# ESP8266_RFID_Schematic.net
KiCad netlist of a schematic drawn in EAGLE
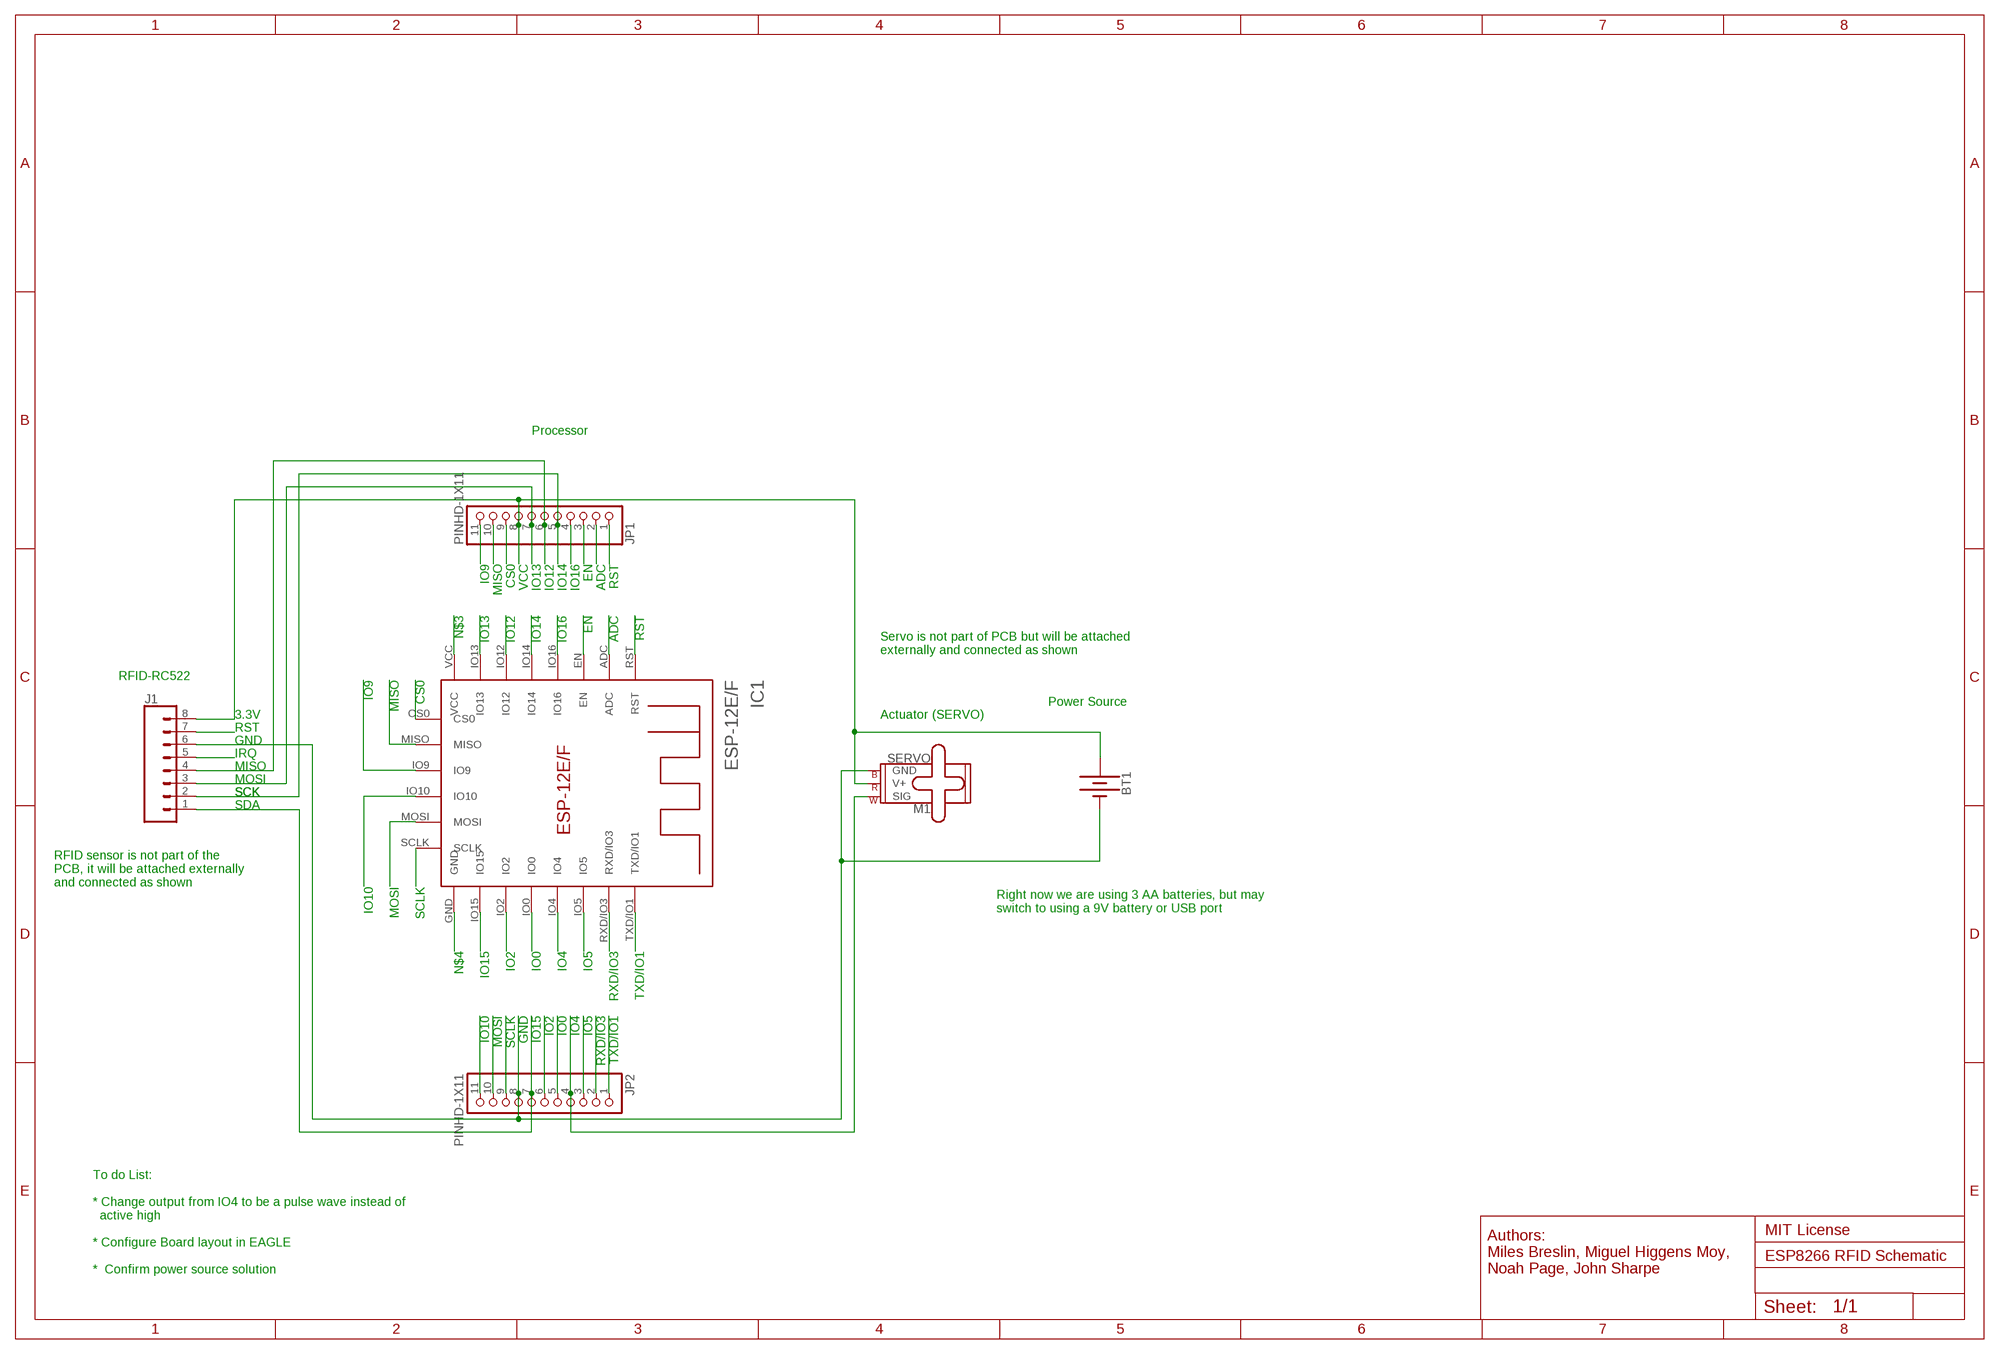
[diagram p0: schematic, sheet 1]

(export (version "E")
  (design (tool "Eeschema 10.0.6"))
  (components
    (comp (ref "BT1")
      (value "BATTERY-AA")
      (footprint "eagle-import:BATTERY-AA")
      (libsource (lib "eagle-import") (part "BATTERY-AA"))
    )
    (comp (ref "IC1")
      (value "ESP-12E/F")
      (footprint "eagle-import:ESP-12E")
      (libsource (lib "eagle-import") (part "ESP-12E/F"))
    )
    (comp (ref "J1")
      (value "CONN_08\"")
      (footprint "eagle-import:1X08")
      (libsource (lib "eagle-import") (part "CONN_08{dblquote}"))
    )
    (comp (ref "JP1")
      (value "PINHD-1X11")
      (footprint "eagle-import:1X11")
      (libsource (lib "eagle-import") (part "PINHD-1X11"))
    )
    (comp (ref "JP2")
      (value "PINHD-1X11")
      (footprint "eagle-import:1X11")
      (libsource (lib "eagle-import") (part "PINHD-1X11"))
    )
    (comp (ref "M1")
      (value "SERVO")
      (footprint "eagle-import:1X03")
      (libsource (lib "eagle-import") (part "SERVO"))
    )
  )
  (nets
    (net (code "1") (name "/ADC") (class "Default")
      (node (ref "IC1") (pin "ADC") (pinfunction "ADC_ADC") (pintype "bidirectional"))
      (node (ref "JP1") (pin "2") (pinfunction "2_2") (pintype "passive"))
    )
    (net (code "2") (name "/CS0") (class "Default")
      (node (ref "IC1") (pin "CS0") (pinfunction "CS0_CS0") (pintype "bidirectional"))
      (node (ref "JP1") (pin "9") (pinfunction "9_9") (pintype "passive"))
    )
    (net (code "3") (name "/EN") (class "Default")
      (node (ref "IC1") (pin "EN") (pinfunction "EN_EN") (pintype "bidirectional"))
      (node (ref "JP1") (pin "3") (pinfunction "3_3") (pintype "passive"))
    )
    (net (code "4") (name "/GND") (class "Default")
      (node (ref "BT1") (pin "GND@1") (pinfunction "-_GND@1") (pintype "power_in"))
      (node (ref "J1") (pin "6") (pinfunction "6_6") (pintype "passive"))
      (node (ref "JP2") (pin "8") (pinfunction "8_8") (pintype "passive"))
      (node (ref "M1") (pin "3") (pinfunction "GND_3") (pintype "bidirectional"))
    )
    (net (code "5") (name "/IO0") (class "Default")
      (node (ref "IC1") (pin "IO0") (pinfunction "IO0_IO0") (pintype "bidirectional"))
      (node (ref "JP2") (pin "5") (pinfunction "5_5") (pintype "passive"))
    )
    (net (code "6") (name "/IO2") (class "Default")
      (node (ref "IC1") (pin "IO2") (pinfunction "IO2_IO2") (pintype "bidirectional"))
      (node (ref "JP2") (pin "6") (pinfunction "6_6") (pintype "passive"))
    )
    (net (code "7") (name "/IO4") (class "Default")
      (node (ref "IC1") (pin "IO4") (pinfunction "IO4_IO4") (pintype "bidirectional"))
      (node (ref "JP2") (pin "4") (pinfunction "4_4") (pintype "passive"))
      (node (ref "M1") (pin "1") (pinfunction "SIG_1") (pintype "bidirectional"))
    )
    (net (code "8") (name "/IO5") (class "Default")
      (node (ref "IC1") (pin "IO5") (pinfunction "IO5_IO5") (pintype "bidirectional"))
      (node (ref "JP2") (pin "3") (pinfunction "3_3") (pintype "passive"))
    )
    (net (code "9") (name "/IO9") (class "Default")
      (node (ref "IC1") (pin "IO9") (pinfunction "IO9_IO9") (pintype "bidirectional"))
      (node (ref "JP1") (pin "11") (pinfunction "11_11") (pintype "passive"))
    )
    (net (code "10") (name "/IO10") (class "Default")
      (node (ref "IC1") (pin "IO10") (pinfunction "IO10_IO10") (pintype "bidirectional"))
      (node (ref "JP2") (pin "11") (pinfunction "11_11") (pintype "passive"))
    )
    (net (code "11") (name "/IO12") (class "Default")
      (node (ref "J1") (pin "4") (pinfunction "4_4") (pintype "passive"))
      (node (ref "JP1") (pin "6") (pinfunction "6_6") (pintype "passive"))
    )
    (net (code "12") (name "/IO13") (class "Default")
      (node (ref "IC1") (pin "IO13") (pinfunction "IO13_IO13") (pintype "bidirectional"))
      (node (ref "J1") (pin "3") (pinfunction "3_3") (pintype "passive"))
      (node (ref "JP1") (pin "7") (pinfunction "7_7") (pintype "passive"))
    )
    (net (code "13") (name "/IO14") (class "Default")
      (node (ref "J1") (pin "2") (pinfunction "2_2") (pintype "passive"))
      (node (ref "JP1") (pin "5") (pinfunction "5_5") (pintype "passive"))
    )
    (net (code "14") (name "/IO15") (class "Default")
      (node (ref "J1") (pin "1") (pinfunction "1_1") (pintype "passive"))
      (node (ref "JP2") (pin "7") (pinfunction "7_7") (pintype "passive"))
    )
    (net (code "15") (name "/IO16") (class "Default")
      (node (ref "IC1") (pin "IO16") (pinfunction "IO16_IO16") (pintype "bidirectional"))
      (node (ref "JP1") (pin "4") (pinfunction "4_4") (pintype "passive"))
    )
    (net (code "16") (name "/MISO") (class "Default")
      (node (ref "IC1") (pin "MISO") (pinfunction "MISO_MISO") (pintype "bidirectional"))
      (node (ref "JP1") (pin "10") (pinfunction "10_10") (pintype "passive"))
    )
    (net (code "17") (name "/MOSI") (class "Default")
      (node (ref "IC1") (pin "MOSI") (pinfunction "MOSI_MOSI") (pintype "bidirectional"))
      (node (ref "JP2") (pin "10") (pinfunction "10_10") (pintype "passive"))
    )
    (net (code "18") (name "/N$3") (class "Default")
      (node (ref "IC1") (pin "VCC") (pinfunction "VCC_VCC") (pintype "power_in"))
    )
    (net (code "19") (name "/N$4") (class "Default")
      (node (ref "IC1") (pin "GND") (pinfunction "GND_GND") (pintype "power_in"))
    )
    (net (code "20") (name "/RST") (class "Default")
      (node (ref "IC1") (pin "RST") (pinfunction "RST_RST") (pintype "input"))
      (node (ref "J1") (pin "7") (pinfunction "7_7") (pintype "passive"))
      (node (ref "JP1") (pin "1") (pinfunction "1_1") (pintype "passive"))
    )
    (net (code "21") (name "/RXD{slash}IO3") (class "Default")
      (node (ref "IC1") (pin "RXD/IO3") (pinfunction "RXD/IO3_RXD/IO3") (pintype "bidirectional"))
      (node (ref "JP2") (pin "2") (pinfunction "2_2") (pintype "passive"))
    )
    (net (code "22") (name "/SCLK") (class "Default")
      (node (ref "IC1") (pin "SCLK") (pinfunction "SCLK_SCLK") (pintype "bidirectional"))
      (node (ref "JP2") (pin "9") (pinfunction "9_9") (pintype "passive"))
    )
    (net (code "23") (name "/TXD{slash}IO1") (class "Default")
      (node (ref "IC1") (pin "TXD/IO1") (pinfunction "TXD/IO1_TXD/IO1") (pintype "bidirectional"))
      (node (ref "JP2") (pin "1") (pinfunction "1_1") (pintype "passive"))
    )
    (net (code "24") (name "/VCC") (class "Default")
      (node (ref "BT1") (pin "PWR@1") (pinfunction "+_PWR@1") (pintype "power_in"))
      (node (ref "J1") (pin "8") (pinfunction "8_8") (pintype "passive"))
      (node (ref "JP1") (pin "8") (pinfunction "8_8") (pintype "passive"))
      (node (ref "M1") (pin "2") (pinfunction "V+_2") (pintype "bidirectional"))
    )
    (net (code "25") (name "unconnected-(IC1-PadIO12)") (class "Default")
      (node (ref "IC1") (pin "IO12") (pinfunction "IO12_IO12") (pintype "bidirectional"))
    )
    (net (code "26") (name "unconnected-(IC1-PadIO14)") (class "Default")
      (node (ref "IC1") (pin "IO14") (pinfunction "IO14_IO14") (pintype "bidirectional"))
    )
    (net (code "27") (name "unconnected-(IC1-PadIO15)") (class "Default")
      (node (ref "IC1") (pin "IO15") (pinfunction "IO15_IO15") (pintype "bidirectional"))
    )
    (net (code "28") (name "unconnected-(J1-Pad5)") (class "Default")
      (node (ref "J1") (pin "5") (pinfunction "5_5") (pintype "passive"))
    )
  )
)
